# gps_tracker.net
KiCad netlist of a schematic drawn in EAGLE
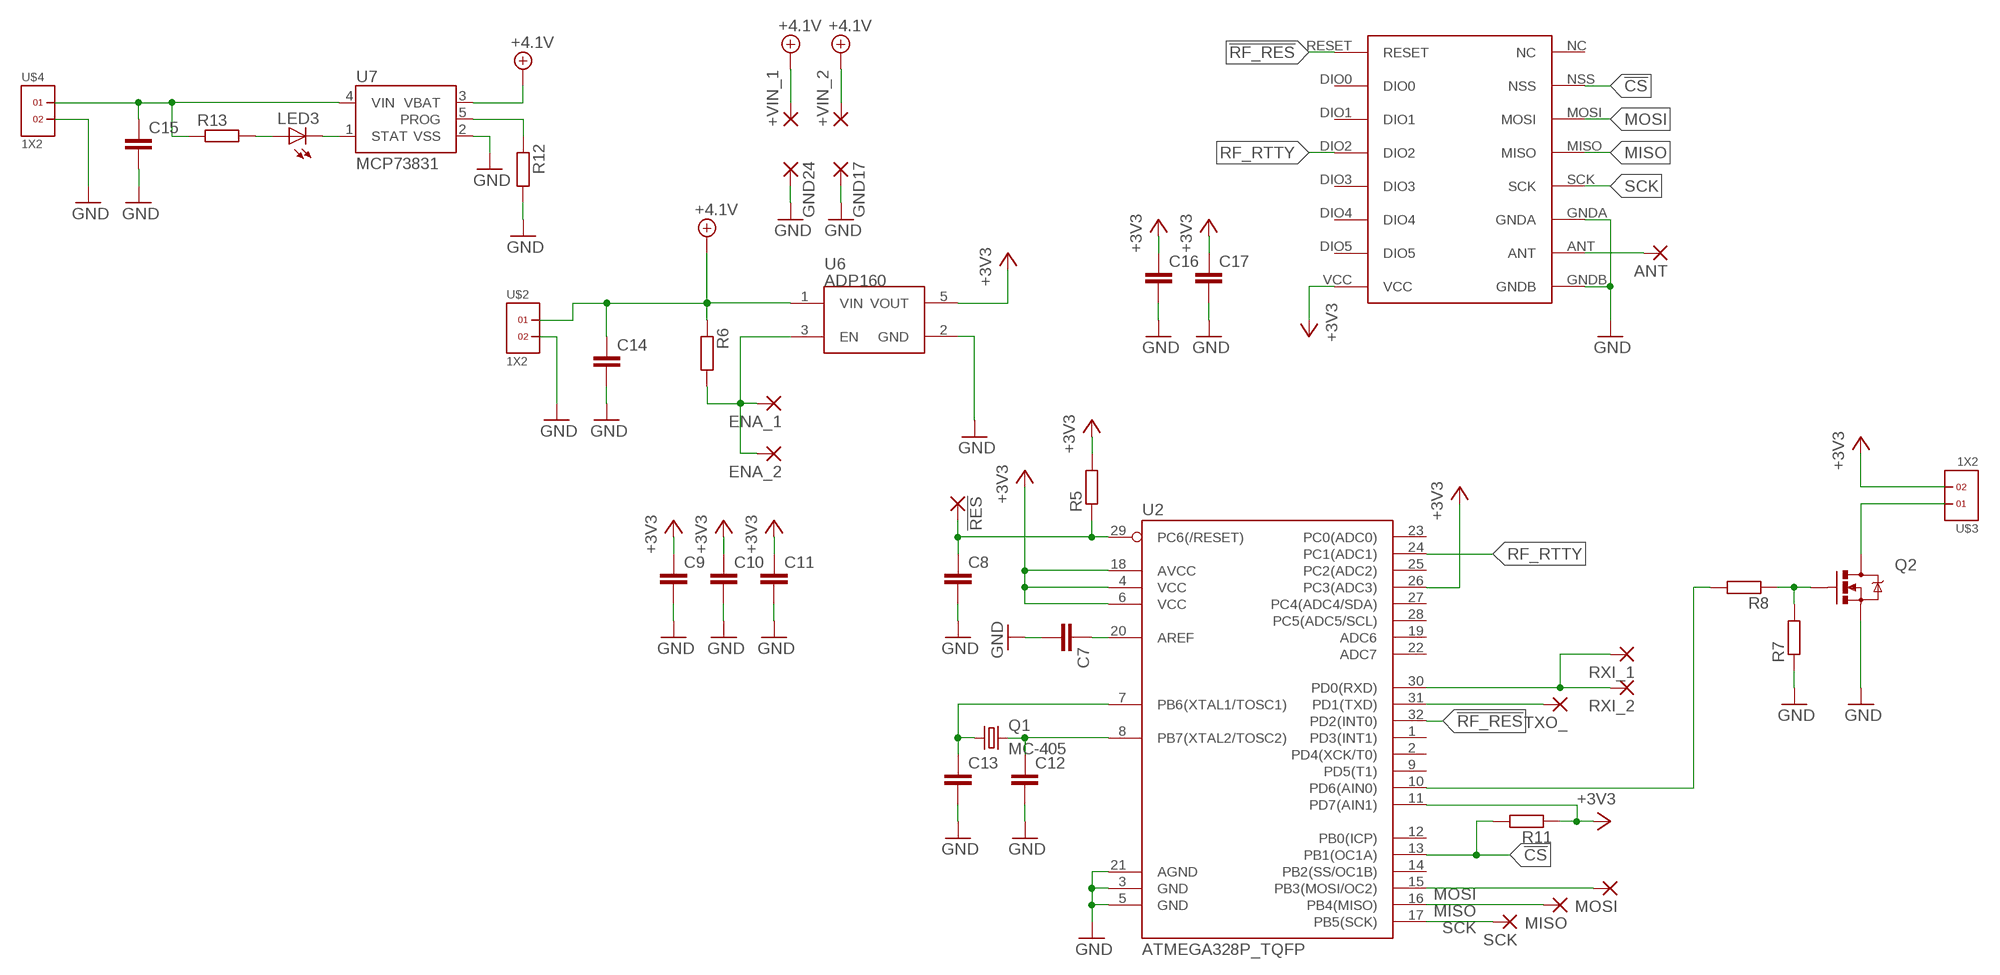
[diagram p0: schematic, sheet 1, part 1 of 2]
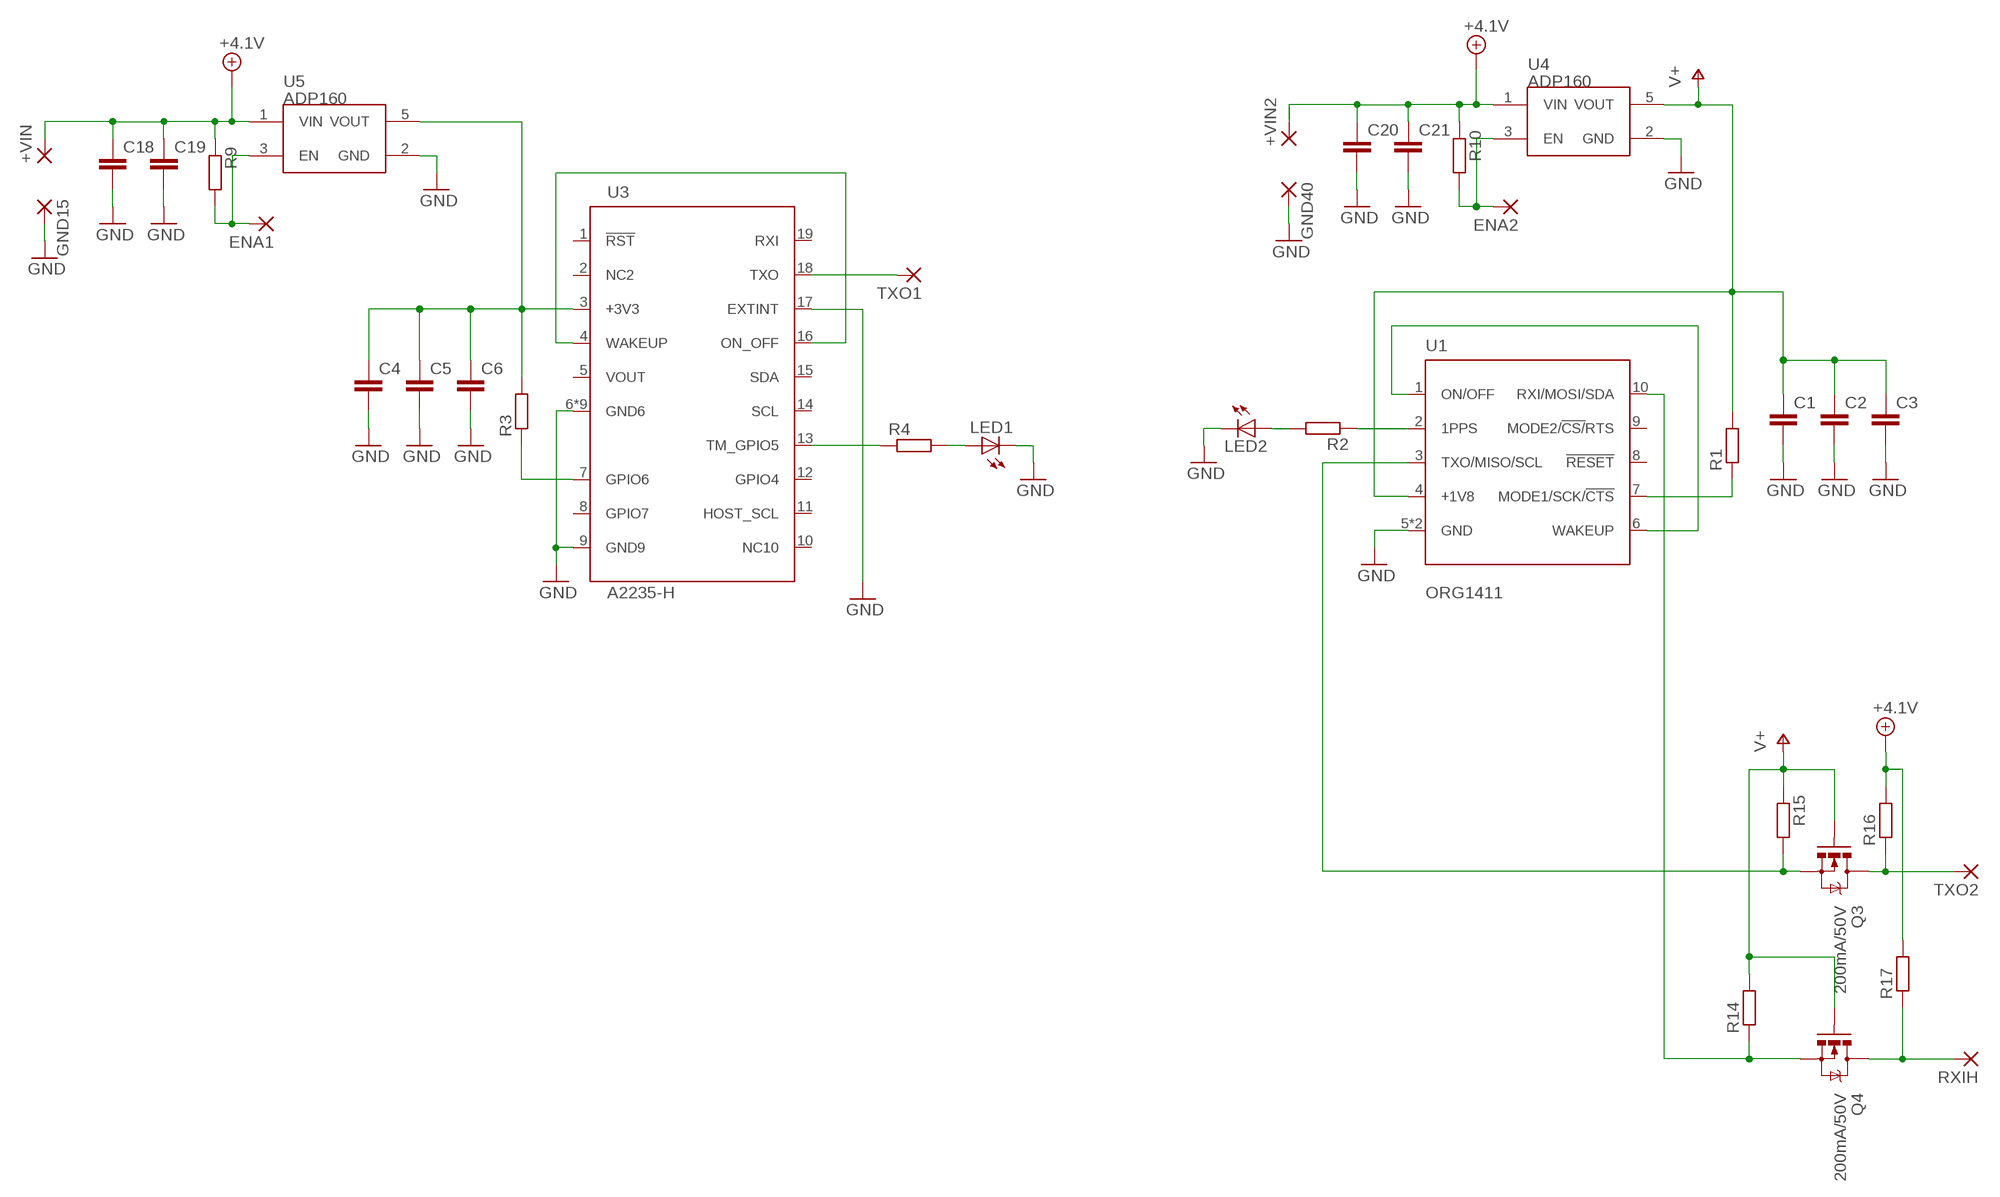
[diagram p1: schematic, sheet 1, part 2 of 2]
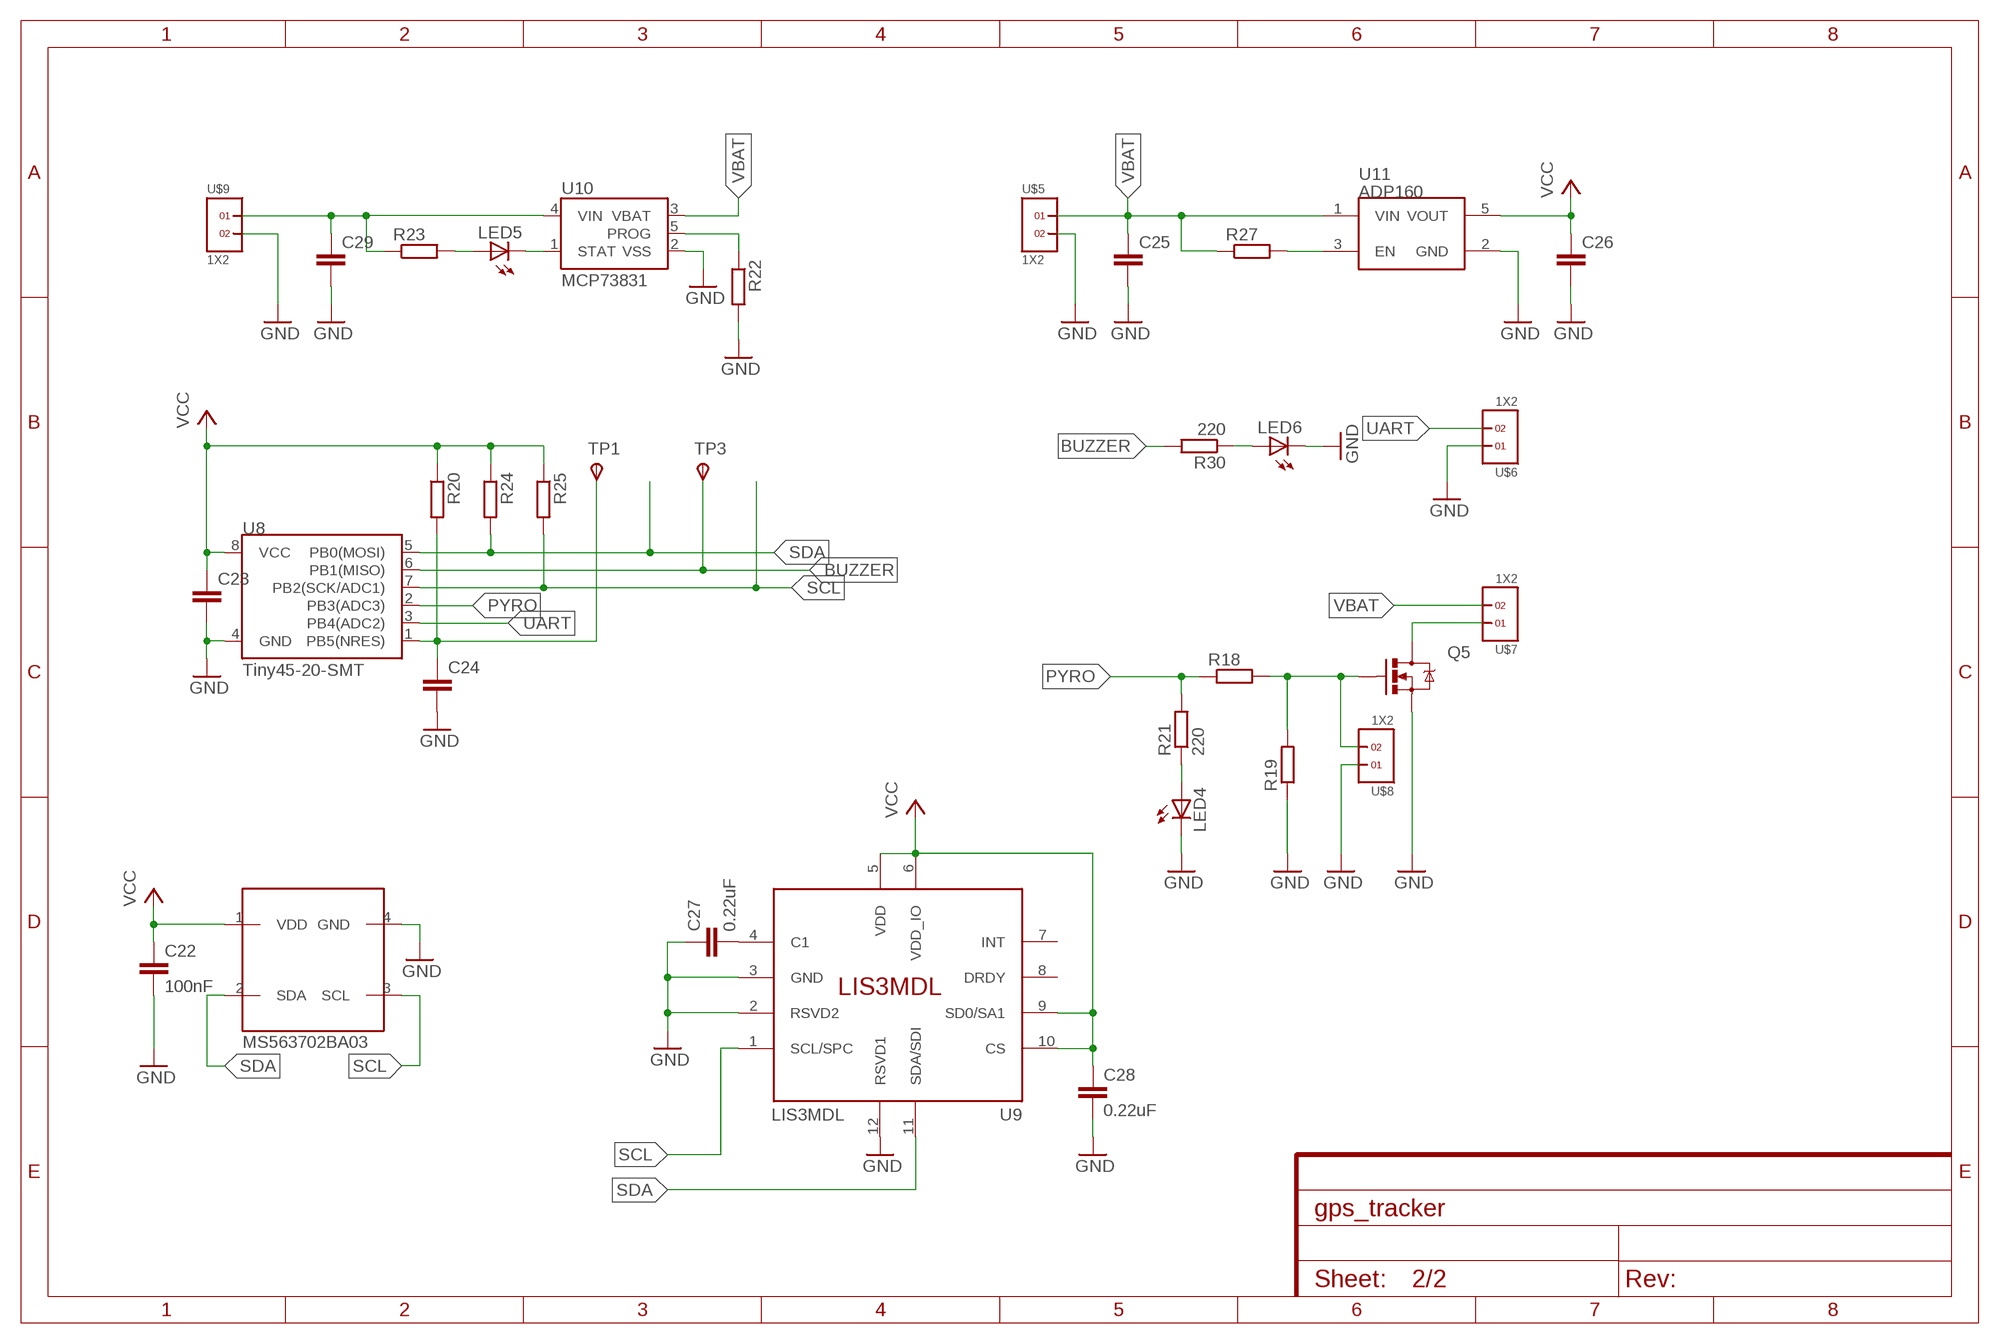
[diagram p2: schematic, sheet 2]

(export (version "E")
  (design (tool "Eeschema 10.0.6"))
  (components
    (comp (ref "C22")
      (value "100nF")
      (footprint "eagle-import:C0603")
      (libsource (lib "eagle-import") (part "C-EUC0603"))
    )
    (comp (ref "C23")
      (value "C-EUC1206")
      (footprint "eagle-import:C1206")
      (libsource (lib "eagle-import") (part "C-EUC1206"))
    )
    (comp (ref "C24")
      (value "C-EUC0603")
      (footprint "eagle-import:C0603")
      (libsource (lib "eagle-import") (part "C-EUC0603"))
    )
    (comp (ref "C25")
      (value "C-EUC0603")
      (footprint "eagle-import:C0603")
      (libsource (lib "eagle-import") (part "C-EUC0603"))
    )
    (comp (ref "C26")
      (value "C-EUC0603")
      (footprint "eagle-import:C0603")
      (libsource (lib "eagle-import") (part "C-EUC0603"))
    )
    (comp (ref "C27")
      (value "0.22uF")
      (footprint "eagle-import:C0603K")
      (libsource (lib "eagle-import") (part "C-EUC0603K"))
    )
    (comp (ref "C28")
      (value "0.22uF")
      (footprint "eagle-import:C0603")
      (libsource (lib "eagle-import") (part "C-EUC0603"))
    )
    (comp (ref "C29")
      (value "C-EUC0603")
      (footprint "eagle-import:C0603")
      (libsource (lib "eagle-import") (part "C-EUC0603"))
    )
    (comp (ref "IC1")
      (value "MS563702BA03")
      (footprint "eagle-import:MS5637")
      (libsource (lib "eagle-import") (part "MS563702BA03"))
    )
    (comp (ref "LED4")
      (value "LEDCHIPLED_0805")
      (footprint "eagle-import:CHIPLED_0805")
      (libsource (lib "eagle-import") (part "LEDCHIPLED_0805"))
    )
    (comp (ref "LED5")
      (value "LEDCHIPLED_0603")
      (footprint "eagle-import:CHIPLED_0603")
      (libsource (lib "eagle-import") (part "LEDCHIPLED_0603"))
    )
    (comp (ref "LED6")
      (value "LEDCHIPLED_0805")
      (footprint "eagle-import:CHIPLED_0805")
      (libsource (lib "eagle-import") (part "LEDCHIPLED_0805"))
    )
    (comp (ref "Q5")
      (value "MOSFET-NCHANNELBSS123LT1G")
      (footprint "eagle-import:SOT23-3")
      (libsource (lib "eagle-import") (part "MOSFET-NCHANNELBSS123LT1G"))
    )
    (comp (ref "R18")
      (value "R-EU_R0603")
      (footprint "eagle-import:R0603")
      (libsource (lib "eagle-import") (part "R-EU_R0603"))
    )
    (comp (ref "R19")
      (value "R-EU_R0603")
      (footprint "eagle-import:R0603")
      (libsource (lib "eagle-import") (part "R-EU_R0603"))
    )
    (comp (ref "R20")
      (value "R-EU_R0603")
      (footprint "eagle-import:R0603")
      (libsource (lib "eagle-import") (part "R-EU_R0603"))
    )
    (comp (ref "R21")
      (value "220")
      (footprint "eagle-import:R0603")
      (libsource (lib "eagle-import") (part "resistor_R-EU_R0603"))
    )
    (comp (ref "R22")
      (value "R-EU_R0603")
      (footprint "eagle-import:R0603")
      (libsource (lib "eagle-import") (part "R-EU_R0603"))
    )
    (comp (ref "R23")
      (value "R-EU_R0603")
      (footprint "eagle-import:R0603")
      (libsource (lib "eagle-import") (part "R-EU_R0603"))
    )
    (comp (ref "R24")
      (value "R-EU_R0603")
      (footprint "eagle-import:R0603")
      (libsource (lib "eagle-import") (part "R-EU_R0603"))
    )
    (comp (ref "R25")
      (value "R-EU_R0603")
      (footprint "eagle-import:R0603")
      (libsource (lib "eagle-import") (part "R-EU_R0603"))
    )
    (comp (ref "R27")
      (value "R-EU_R0603")
      (footprint "eagle-import:R0603")
      (libsource (lib "eagle-import") (part "R-EU_R0603"))
    )
    (comp (ref "R30")
      (value "220")
      (footprint "eagle-import:R0603")
      (libsource (lib "eagle-import") (part "resistor_R-EU_R0603"))
    )
    (comp (ref "TP1")
      (value "TPSB1,27")
      (footprint "eagle-import:B1,27")
      (libsource (lib "eagle-import") (part "TPSB1,27"))
    )
    (comp (ref "TP3")
      (value "TPSB1,27")
      (footprint "eagle-import:B1,27")
      (libsource (lib "eagle-import") (part "TPSB1,27"))
    )
    (comp (ref "U$5")
      (value "1X2")
      (footprint "eagle-import:1X2")
      (libsource (lib "eagle-import") (part "1X2"))
    )
    (comp (ref "U$6")
      (value "1X2")
      (footprint "eagle-import:1X2")
      (libsource (lib "eagle-import") (part "1X2"))
    )
    (comp (ref "U$7")
      (value "1X2")
      (footprint "eagle-import:1X2")
      (libsource (lib "eagle-import") (part "1X2"))
    )
    (comp (ref "U$8")
      (value "1X2")
      (footprint "eagle-import:1X2")
      (libsource (lib "eagle-import") (part "1X2"))
    )
    (comp (ref "U$9")
      (value "1X2")
      (footprint "eagle-import:1X2")
      (libsource (lib "eagle-import") (part "1X2"))
    )
    (comp (ref "U8")
      (value "Tiny45-20-SMT")
      (footprint "eagle-import:SO08-EIAJ")
      (libsource (lib "eagle-import") (part "ATTINY45TINY45-20-SMT"))
    )
    (comp (ref "U9")
      (value "LIS3MDL")
      (footprint "eagle-import:VFLGA-12")
      (libsource (lib "eagle-import") (part "LIS3MDL"))
    )
    (comp (ref "U10")
      (value "MCP73831")
      (footprint "eagle-import:SOT23-5")
      (libsource (lib "eagle-import") (part "MCP73831"))
    )
    (comp (ref "U11")
      (value "ADP160")
      (footprint "eagle-import:SOT23-5")
      (libsource (lib "eagle-import") (part "ADP160"))
    )
    (comp (ref "!RES")
      (value "SMD2")
      (footprint "eagle-import:SMD1,27-2,54")
      (libsource (lib "eagle-import") (part "SMD2"))
    )
    (comp (ref "+VIN")
      (value "SMD2")
      (footprint "eagle-import:SMD1,27-2,54")
      (libsource (lib "eagle-import") (part "SMD2"))
    )
    (comp (ref "+VIN2")
      (value "SMD2")
      (footprint "eagle-import:SMD1,27-2,54")
      (libsource (lib "eagle-import") (part "SMD2"))
    )
    (comp (ref "+VIN_1")
      (value "SMD2")
      (footprint "eagle-import:SMD1,27-2,54")
      (libsource (lib "eagle-import") (part "SMD2"))
    )
    (comp (ref "+VIN_2")
      (value "SMD2")
      (footprint "eagle-import:SMD1,27-2,54")
      (libsource (lib "eagle-import") (part "SMD2"))
    )
    (comp (ref "ANT")
      (value "SMD2")
      (footprint "eagle-import:SMD1,27-2,54")
      (libsource (lib "eagle-import") (part "SMD2"))
    )
    (comp (ref "C1")
      (value "C-EUC0603")
      (footprint "eagle-import:C0603")
      (libsource (lib "eagle-import") (part "C-EUC0603"))
    )
    (comp (ref "C2")
      (value "C-EUC0603")
      (footprint "eagle-import:C0603")
      (libsource (lib "eagle-import") (part "C-EUC0603"))
    )
    (comp (ref "C3")
      (value "C-EUC0603")
      (footprint "eagle-import:C0603")
      (libsource (lib "eagle-import") (part "C-EUC0603"))
    )
    (comp (ref "C4")
      (value "C-EUC0603")
      (footprint "eagle-import:C0603")
      (libsource (lib "eagle-import") (part "C-EUC0603"))
    )
    (comp (ref "C5")
      (value "C-EUC0603")
      (footprint "eagle-import:C0603")
      (libsource (lib "eagle-import") (part "C-EUC0603"))
    )
    (comp (ref "C6")
      (value "C-EUC0603")
      (footprint "eagle-import:C0603")
      (libsource (lib "eagle-import") (part "C-EUC0603"))
    )
    (comp (ref "C7")
      (value "C-EUC0603")
      (footprint "eagle-import:C0603")
      (libsource (lib "eagle-import") (part "C-EUC0603"))
    )
    (comp (ref "C8")
      (value "C-EUC0603")
      (footprint "eagle-import:C0603")
      (libsource (lib "eagle-import") (part "C-EUC0603"))
    )
    (comp (ref "C9")
      (value "C-EUC0603")
      (footprint "eagle-import:C0603")
      (libsource (lib "eagle-import") (part "C-EUC0603"))
    )
    (comp (ref "C10")
      (value "C-EUC0603")
      (footprint "eagle-import:C0603")
      (libsource (lib "eagle-import") (part "C-EUC0603"))
    )
    (comp (ref "C11")
      (value "C-EUC0603")
      (footprint "eagle-import:C0603")
      (libsource (lib "eagle-import") (part "C-EUC0603"))
    )
    (comp (ref "C12")
      (value "C-EUC0603")
      (footprint "eagle-import:C0603")
      (libsource (lib "eagle-import") (part "C-EUC0603"))
    )
    (comp (ref "C13")
      (value "C-EUC0603")
      (footprint "eagle-import:C0603")
      (libsource (lib "eagle-import") (part "C-EUC0603"))
    )
    (comp (ref "C14")
      (value "C-EUC0603")
      (footprint "eagle-import:C0603")
      (libsource (lib "eagle-import") (part "C-EUC0603"))
    )
    (comp (ref "C15")
      (value "C-EUC0603")
      (footprint "eagle-import:C0603")
      (libsource (lib "eagle-import") (part "C-EUC0603"))
    )
    (comp (ref "C16")
      (value "C-EUC0603")
      (footprint "eagle-import:C0603")
      (libsource (lib "eagle-import") (part "C-EUC0603"))
    )
    (comp (ref "C17")
      (value "C-EUC0603")
      (footprint "eagle-import:C0603")
      (libsource (lib "eagle-import") (part "C-EUC0603"))
    )
    (comp (ref "C18")
      (value "C-EUC0603")
      (footprint "eagle-import:C0603")
      (libsource (lib "eagle-import") (part "C-EUC0603"))
    )
    (comp (ref "C19")
      (value "C-EUC0603")
      (footprint "eagle-import:C0603")
      (libsource (lib "eagle-import") (part "C-EUC0603"))
    )
    (comp (ref "C20")
      (value "C-EUC0603")
      (footprint "eagle-import:C0603")
      (libsource (lib "eagle-import") (part "C-EUC0603"))
    )
    (comp (ref "C21")
      (value "C-EUC0603")
      (footprint "eagle-import:C0603")
      (libsource (lib "eagle-import") (part "C-EUC0603"))
    )
    (comp (ref "ENA1")
      (value "SMD2")
      (footprint "eagle-import:SMD1,27-2,54")
      (libsource (lib "eagle-import") (part "SMD2"))
    )
    (comp (ref "ENA2")
      (value "SMD2")
      (footprint "eagle-import:SMD1,27-2,54")
      (libsource (lib "eagle-import") (part "SMD2"))
    )
    (comp (ref "ENA_1")
      (value "SMD2")
      (footprint "eagle-import:SMD1,27-2,54")
      (libsource (lib "eagle-import") (part "SMD2"))
    )
    (comp (ref "ENA_2")
      (value "SMD2")
      (footprint "eagle-import:SMD1,27-2,54")
      (libsource (lib "eagle-import") (part "SMD2"))
    )
    (comp (ref "GND15")
      (value "SMD2")
      (footprint "eagle-import:SMD1,27-2,54")
      (libsource (lib "eagle-import") (part "SMD2"))
    )
    (comp (ref "GND17")
      (value "SMD2")
      (footprint "eagle-import:SMD1,27-2,54")
      (libsource (lib "eagle-import") (part "SMD2"))
    )
    (comp (ref "GND24")
      (value "SMD2")
      (footprint "eagle-import:SMD1,27-2,54")
      (libsource (lib "eagle-import") (part "SMD2"))
    )
    (comp (ref "GND40")
      (value "SMD2")
      (footprint "eagle-import:SMD1,27-2,54")
      (libsource (lib "eagle-import") (part "SMD2"))
    )
    (comp (ref "LED1")
      (value "LEDCHIPLED_0603")
      (footprint "eagle-import:CHIPLED_0603")
      (libsource (lib "eagle-import") (part "LEDCHIPLED_0603"))
    )
    (comp (ref "LED2")
      (value "LEDCHIPLED_0603")
      (footprint "eagle-import:CHIPLED_0603")
      (libsource (lib "eagle-import") (part "LEDCHIPLED_0603"))
    )
    (comp (ref "LED3")
      (value "LEDCHIPLED_0603")
      (footprint "eagle-import:CHIPLED_0603")
      (libsource (lib "eagle-import") (part "LEDCHIPLED_0603"))
    )
    (comp (ref "MISO")
      (value "SMD2")
      (footprint "eagle-import:SMD1,27-2,54")
      (libsource (lib "eagle-import") (part "SMD2"))
    )
    (comp (ref "MOSI")
      (value "SMD2")
      (footprint "eagle-import:SMD1,27-2,54")
      (libsource (lib "eagle-import") (part "SMD2"))
    )
    (comp (ref "Q1")
      (value "MC-405")
      (footprint "eagle-import:MC-405")
      (libsource (lib "eagle-import") (part "MC-405"))
    )
    (comp (ref "Q2")
      (value "MOSFET-NCHANNELAO3404A")
      (footprint "eagle-import:SOT23-3")
      (libsource (lib "eagle-import") (part "MOSFET-NCHANNELAO3404A"))
    )
    (comp (ref "Q3")
      (value "200mA/50V")
      (footprint "eagle-import:SOT23-3")
      (libsource (lib "eagle-import") (part "MOSFET-NCHANNELBSS138"))
    )
    (comp (ref "Q4")
      (value "200mA/50V")
      (footprint "eagle-import:SOT23-3")
      (libsource (lib "eagle-import") (part "MOSFET-NCHANNELBSS138"))
    )
    (comp (ref "R1")
      (value "R-EU_R0603")
      (footprint "eagle-import:R0603")
      (libsource (lib "eagle-import") (part "R-EU_R0603"))
    )
    (comp (ref "R2")
      (value "R-EU_R0603")
      (footprint "eagle-import:R0603")
      (libsource (lib "eagle-import") (part "R-EU_R0603"))
    )
    (comp (ref "R3")
      (value "R-EU_R0603")
      (footprint "eagle-import:R0603")
      (libsource (lib "eagle-import") (part "R-EU_R0603"))
    )
    (comp (ref "R4")
      (value "R-EU_R0603")
      (footprint "eagle-import:R0603")
      (libsource (lib "eagle-import") (part "R-EU_R0603"))
    )
    (comp (ref "R5")
      (value "R-EU_R0603")
      (footprint "eagle-import:R0603")
      (libsource (lib "eagle-import") (part "R-EU_R0603"))
    )
    (comp (ref "R6")
      (value "R-EU_R0603")
      (footprint "eagle-import:R0603")
      (libsource (lib "eagle-import") (part "R-EU_R0603"))
    )
    (comp (ref "R7")
      (value "R-EU_R0603")
      (footprint "eagle-import:R0603")
      (libsource (lib "eagle-import") (part "R-EU_R0603"))
    )
    (comp (ref "R8")
      (value "R-EU_R0603")
      (footprint "eagle-import:R0603")
      (libsource (lib "eagle-import") (part "R-EU_R0603"))
    )
    (comp (ref "R9")
      (value "R-EU_R0603")
      (footprint "eagle-import:R0603")
      (libsource (lib "eagle-import") (part "R-EU_R0603"))
    )
    (comp (ref "R10")
      (value "R-EU_R0603")
      (footprint "eagle-import:R0603")
      (libsource (lib "eagle-import") (part "R-EU_R0603"))
    )
    (comp (ref "R11")
      (value "R-EU_R0603")
      (footprint "eagle-import:R0603")
      (libsource (lib "eagle-import") (part "R-EU_R0603"))
    )
    (comp (ref "R12")
      (value "R-EU_R0603")
      (footprint "eagle-import:R0603")
      (libsource (lib "eagle-import") (part "R-EU_R0603"))
    )
    (comp (ref "R13")
      (value "R-EU_R0603")
      (footprint "eagle-import:R0603")
      (libsource (lib "eagle-import") (part "R-EU_R0603"))
    )
    (comp (ref "R14")
      (value "R-EU_R0603")
      (footprint "eagle-import:R0603")
      (libsource (lib "eagle-import") (part "R-EU_R0603"))
    )
    (comp (ref "R15")
      (value "R-EU_R0603")
      (footprint "eagle-import:R0603")
      (libsource (lib "eagle-import") (part "R-EU_R0603"))
    )
    (comp (ref "R16")
      (value "R-EU_R1206")
      (footprint "eagle-import:R1206")
      (libsource (lib "eagle-import") (part "R-EU_R1206"))
    )
    (comp (ref "R17")
      (value "R-EU_R1206")
      (footprint "eagle-import:R1206")
      (libsource (lib "eagle-import") (part "R-EU_R1206"))
    )
    (comp (ref "RXIH")
      (value "SMD2")
      (footprint "eagle-import:SMD1,27-2,54")
      (libsource (lib "eagle-import") (part "SMD2"))
    )
    (comp (ref "RXI_1")
      (value "SMD2")
      (footprint "eagle-import:SMD1,27-2,54")
      (libsource (lib "eagle-import") (part "SMD2"))
    )
    (comp (ref "RXI_2")
      (value "SMD2")
      (footprint "eagle-import:SMD1,27-2,54")
      (libsource (lib "eagle-import") (part "SMD2"))
    )
    (comp (ref "SCK")
      (value "SMD2")
      (footprint "eagle-import:SMD1,27-2,54")
      (libsource (lib "eagle-import") (part "SMD2"))
    )
    (comp (ref "TXO1")
      (value "SMD2")
      (footprint "eagle-import:SMD1,27-2,54")
      (libsource (lib "eagle-import") (part "SMD2"))
    )
    (comp (ref "TXO2")
      (value "SMD2")
      (footprint "eagle-import:SMD1,27-2,54")
      (libsource (lib "eagle-import") (part "SMD2"))
    )
    (comp (ref "TXO_")
      (value "SMD2")
      (footprint "eagle-import:SMD1,27-2,54")
      (libsource (lib "eagle-import") (part "SMD2"))
    )
    (comp (ref "U$1")
      (value "RFM69HW")
      (footprint "eagle-import:RFM")
      (libsource (lib "eagle-import") (part "RFM69HW"))
    )
    (comp (ref "U$2")
      (value "1X2")
      (footprint "eagle-import:1X2")
      (libsource (lib "eagle-import") (part "1X2"))
    )
    (comp (ref "U$3")
      (value "1X2")
      (footprint "eagle-import:1X2")
      (libsource (lib "eagle-import") (part "1X2"))
    )
    (comp (ref "U$4")
      (value "1X2")
      (footprint "eagle-import:1X2")
      (libsource (lib "eagle-import") (part "1X2"))
    )
    (comp (ref "U1")
      (value "ORG1411")
      (footprint "eagle-import:ORG1411")
      (libsource (lib "eagle-import") (part "ORG1411"))
    )
    (comp (ref "U2")
      (value "ATMEGA328P_TQFP")
      (footprint "eagle-import:TQFP32-08")
      (libsource (lib "eagle-import") (part "ATMEGA328P_TQFP"))
    )
    (comp (ref "U3")
      (value "A2235-H")
      (footprint "eagle-import:A2235-H")
      (libsource (lib "eagle-import") (part "A2235-H"))
    )
    (comp (ref "U4")
      (value "ADP160")
      (footprint "eagle-import:SOT23-5")
      (libsource (lib "eagle-import") (part "ADP160"))
    )
    (comp (ref "U5")
      (value "ADP160")
      (footprint "eagle-import:SOT23-5")
      (libsource (lib "eagle-import") (part "ADP160"))
    )
    (comp (ref "U6")
      (value "ADP160")
      (footprint "eagle-import:SOT23-5")
      (libsource (lib "eagle-import") (part "ADP160"))
    )
    (comp (ref "U7")
      (value "MCP73831")
      (footprint "eagle-import:SOT23-5")
      (libsource (lib "eagle-import") (part "MCP73831"))
    )
  )
  (nets
    (net (code "1") (name "+3V3") (class "Default")
      (node (ref "C10") (pin "1") (pinfunction "1_1") (pintype "passive"))
      (node (ref "C11") (pin "1") (pinfunction "1_1") (pintype "passive"))
      (node (ref "C16") (pin "1") (pinfunction "1_1") (pintype "passive"))
      (node (ref "C17") (pin "1") (pinfunction "1_1") (pintype "passive"))
      (node (ref "C9") (pin "1") (pinfunction "1_1") (pintype "passive"))
      (node (ref "R11") (pin "1") (pinfunction "1_1") (pintype "passive"))
      (node (ref "R5") (pin "2") (pinfunction "2_2") (pintype "passive"))
      (node (ref "U$1") (pin "VCC") (pinfunction "VCC_VCC") (pintype "bidirectional"))
      (node (ref "U$3") (pin "2") (pinfunction "2_2") (pintype "bidirectional"))
      (node (ref "U2") (pin "11") (pinfunction "PD7(AIN1)_11") (pintype "bidirectional"))
      (node (ref "U2") (pin "18") (pinfunction "AVCC_18") (pintype "bidirectional"))
      (node (ref "U2") (pin "26") (pinfunction "PC3(ADC3)_26") (pintype "bidirectional"))
      (node (ref "U2") (pin "4") (pinfunction "VCC_4") (pintype "bidirectional"))
      (node (ref "U2") (pin "6") (pinfunction "VCC_6") (pintype "bidirectional"))
      (node (ref "U6") (pin "5") (pinfunction "VOUT_5") (pintype "bidirectional"))
    )
    (net (code "2") (name "+4.1V") (class "Default")
      (node (ref "+VIN") (pin "1") (pinfunction "P_1") (pintype "passive"))
      (node (ref "+VIN2") (pin "1") (pinfunction "P_1") (pintype "passive"))
      (node (ref "+VIN_1") (pin "1") (pinfunction "P_1") (pintype "passive"))
      (node (ref "+VIN_2") (pin "1") (pinfunction "P_1") (pintype "passive"))
      (node (ref "C14") (pin "1") (pinfunction "1_1") (pintype "passive"))
      (node (ref "C18") (pin "1") (pinfunction "1_1") (pintype "passive"))
      (node (ref "C19") (pin "1") (pinfunction "1_1") (pintype "passive"))
      (node (ref "C20") (pin "1") (pinfunction "1_1") (pintype "passive"))
      (node (ref "C21") (pin "1") (pinfunction "1_1") (pintype "passive"))
      (node (ref "R10") (pin "1") (pinfunction "1_1") (pintype "passive"))
      (node (ref "R16") (pin "2") (pinfunction "2_2") (pintype "passive"))
      (node (ref "R17") (pin "2") (pinfunction "2_2") (pintype "passive"))
      (node (ref "R6") (pin "1") (pinfunction "1_1") (pintype "passive"))
      (node (ref "R9") (pin "1") (pinfunction "1_1") (pintype "passive"))
      (node (ref "U$2") (pin "1") (pinfunction "1_1") (pintype "bidirectional"))
      (node (ref "U4") (pin "1") (pinfunction "VIN_1") (pintype "bidirectional"))
      (node (ref "U5") (pin "1") (pinfunction "VIN_1") (pintype "bidirectional"))
      (node (ref "U6") (pin "1") (pinfunction "VIN_1") (pintype "bidirectional"))
      (node (ref "U7") (pin "3") (pinfunction "VBAT_3") (pintype "power_in"))
    )
    (net (code "3") (name "BUZZER") (class "Default")
      (node (ref "R30") (pin "2") (pinfunction "2_2") (pintype "passive"))
      (node (ref "TP3") (pin "TP") (pinfunction "PP_TP") (pintype "input"))
      (node (ref "U8") (pin "6") (pinfunction "PB1(MISO)_6") (pintype "bidirectional"))
    )
    (net (code "4") (name "GND") (class "Default")
      (node (ref "C1") (pin "2") (pinfunction "2_2") (pintype "passive"))
      (node (ref "C10") (pin "2") (pinfunction "2_2") (pintype "passive"))
      (node (ref "C11") (pin "2") (pinfunction "2_2") (pintype "passive"))
      (node (ref "C12") (pin "2") (pinfunction "2_2") (pintype "passive"))
      (node (ref "C13") (pin "2") (pinfunction "2_2") (pintype "passive"))
      (node (ref "C14") (pin "2") (pinfunction "2_2") (pintype "passive"))
      (node (ref "C15") (pin "2") (pinfunction "2_2") (pintype "passive"))
      (node (ref "C16") (pin "2") (pinfunction "2_2") (pintype "passive"))
      (node (ref "C17") (pin "2") (pinfunction "2_2") (pintype "passive"))
      (node (ref "C18") (pin "2") (pinfunction "2_2") (pintype "passive"))
      (node (ref "C19") (pin "2") (pinfunction "2_2") (pintype "passive"))
      (node (ref "C2") (pin "2") (pinfunction "2_2") (pintype "passive"))
      (node (ref "C20") (pin "2") (pinfunction "2_2") (pintype "passive"))
      (node (ref "C21") (pin "2") (pinfunction "2_2") (pintype "passive"))
      (node (ref "C22") (pin "2") (pinfunction "2_2") (pintype "passive"))
      (node (ref "C23") (pin "2") (pinfunction "2_2") (pintype "passive"))
      (node (ref "C24") (pin "2") (pinfunction "2_2") (pintype "passive"))
      (node (ref "C25") (pin "2") (pinfunction "2_2") (pintype "passive"))
      (node (ref "C26") (pin "2") (pinfunction "2_2") (pintype "passive"))
      (node (ref "C27") (pin "1") (pinfunction "1_1") (pintype "passive"))
      (node (ref "C28") (pin "2") (pinfunction "2_2") (pintype "passive"))
      (node (ref "C29") (pin "2") (pinfunction "2_2") (pintype "passive"))
      (node (ref "C3") (pin "2") (pinfunction "2_2") (pintype "passive"))
      (node (ref "C4") (pin "2") (pinfunction "2_2") (pintype "passive"))
      (node (ref "C5") (pin "2") (pinfunction "2_2") (pintype "passive"))
      (node (ref "C6") (pin "2") (pinfunction "2_2") (pintype "passive"))
      (node (ref "C7") (pin "2") (pinfunction "2_2") (pintype "passive"))
      (node (ref "C8") (pin "2") (pinfunction "2_2") (pintype "passive"))
      (node (ref "C9") (pin "2") (pinfunction "2_2") (pintype "passive"))
      (node (ref "GND15") (pin "1") (pinfunction "P_1") (pintype "passive"))
      (node (ref "GND17") (pin "1") (pinfunction "P_1") (pintype "passive"))
      (node (ref "GND24") (pin "1") (pinfunction "P_1") (pintype "passive"))
      (node (ref "GND40") (pin "1") (pinfunction "P_1") (pintype "passive"))
      (node (ref "IC1") (pin "4") (pinfunction "GND_4") (pintype "bidirectional"))
      (node (ref "LED1") (pin "C") (pinfunction "C_C") (pintype "passive"))
      (node (ref "LED2") (pin "C") (pinfunction "C_C") (pintype "passive"))
      (node (ref "LED4") (pin "C") (pinfunction "C_C") (pintype "passive"))
      (node (ref "LED6") (pin "C") (pinfunction "C_C") (pintype "passive"))
      (node (ref "Q2") (pin "2") (pinfunction "S_2") (pintype "passive"))
      (node (ref "Q5") (pin "2") (pinfunction "S_2") (pintype "passive"))
      (node (ref "R12") (pin "2") (pinfunction "2_2") (pintype "passive"))
      (node (ref "R19") (pin "1") (pinfunction "1_1") (pintype "passive"))
      (node (ref "R22") (pin "2") (pinfunction "2_2") (pintype "passive"))
      (node (ref "R7") (pin "1") (pinfunction "1_1") (pintype "passive"))
      (node (ref "U$1") (pin "GNDA") (pinfunction "GNDA_GNDA") (pintype "bidirectional"))
      (node (ref "U$1") (pin "GNDB") (pinfunction "GNDB_GNDB") (pintype "bidirectional"))
      (node (ref "U$2") (pin "2") (pinfunction "2_2") (pintype "bidirectional"))
      (node (ref "U$4") (pin "2") (pinfunction "2_2") (pintype "bidirectional"))
      (node (ref "U$5") (pin "2") (pinfunction "2_2") (pintype "bidirectional"))
      (node (ref "U$6") (pin "1") (pinfunction "1_1") (pintype "bidirectional"))
      (node (ref "U$8") (pin "1") (pinfunction "1_1") (pintype "bidirectional"))
      (node (ref "U$9") (pin "2") (pinfunction "2_2") (pintype "bidirectional"))
      (node (ref "U1") (pin "11") (pinfunction "GND_11") (pintype "power_in"))
      (node (ref "U1") (pin "5") (pinfunction "GND_5") (pintype "power_in"))
      (node (ref "U10") (pin "2") (pinfunction "VSS_2") (pintype "power_in"))
      (node (ref "U11") (pin "2") (pinfunction "GND_2") (pintype "bidirectional"))
      (node (ref "U2") (pin "21") (pinfunction "AGND_21") (pintype "bidirectional"))
      (node (ref "U2") (pin "3") (pinfunction "GND_3") (pintype "bidirectional"))
      (node (ref "U2") (pin "5") (pinfunction "GND_5") (pintype "bidirectional"))
      (node (ref "U3") (pin "101") (pinfunction "GND6_101") (pintype "power_in"))
      (node (ref "U3") (pin "102") (pinfunction "GND6_102") (pintype "power_in"))
      (node (ref "U3") (pin "103") (pinfunction "GND6_103") (pintype "power_in"))
      (node (ref "U3") (pin "104") (pinfunction "GND6_104") (pintype "power_in"))
      (node (ref "U3") (pin "105") (pinfunction "GND6_105") (pintype "power_in"))
      (node (ref "U3") (pin "106") (pinfunction "GND6_106") (pintype "power_in"))
      (node (ref "U3") (pin "107") (pinfunction "GND6_107") (pintype "power_in"))
      (node (ref "U3") (pin "108") (pinfunction "GND6_108") (pintype "power_in"))
      (node (ref "U3") (pin "17") (pinfunction "EXTINT_17") (pintype "input"))
      (node (ref "U3") (pin "6") (pinfunction "GND6_6") (pintype "power_in"))
      (node (ref "U3") (pin "9") (pinfunction "GND9_9") (pintype "power_in"))
      (node (ref "U4") (pin "2") (pinfunction "GND_2") (pintype "bidirectional"))
      (node (ref "U5") (pin "2") (pinfunction "GND_2") (pintype "bidirectional"))
      (node (ref "U6") (pin "2") (pinfunction "GND_2") (pintype "bidirectional"))
      (node (ref "U7") (pin "2") (pinfunction "VSS_2") (pintype "power_in"))
      (node (ref "U8") (pin "4") (pinfunction "GND_4") (pintype "bidirectional"))
      (node (ref "U9") (pin "12") (pinfunction "RSVD1_12") (pintype "bidirectional"))
      (node (ref "U9") (pin "2") (pinfunction "RSVD2_2") (pintype "bidirectional"))
      (node (ref "U9") (pin "3") (pinfunction "GND_3") (pintype "power_in"))
    )
    (net (code "5") (name "MISO") (class "Default")
      (node (ref "MISO") (pin "1") (pinfunction "P_1") (pintype "passive"))
      (node (ref "U$1") (pin "MISO") (pinfunction "MISO_MISO") (pintype "bidirectional"))
      (node (ref "U2") (pin "16") (pinfunction "PB4(MISO)_16") (pintype "bidirectional"))
    )
    (net (code "6") (name "MOSI") (class "Default")
      (node (ref "MOSI") (pin "1") (pinfunction "P_1") (pintype "passive"))
      (node (ref "U$1") (pin "MOSI") (pinfunction "MOSI_MOSI") (pintype "bidirectional"))
      (node (ref "U2") (pin "15") (pinfunction "PB3(MOSI/OC2)_15") (pintype "bidirectional"))
    )
    (net (code "7") (name "Net-(!RES-P)") (class "Default")
      (node (ref "!RES") (pin "1") (pinfunction "P_1") (pintype "passive"))
      (node (ref "C8") (pin "1") (pinfunction "1_1") (pintype "passive"))
      (node (ref "R5") (pin "1") (pinfunction "1_1") (pintype "passive"))
      (node (ref "U2") (pin "29") (pinfunction "PC6(/RESET)_29") (pintype "bidirectional"))
    )
    (net (code "8") (name "Net-(ANT-P)") (class "Default")
      (node (ref "ANT") (pin "1") (pinfunction "P_1") (pintype "passive"))
      (node (ref "U$1") (pin "ANT") (pinfunction "ANT_ANT") (pintype "bidirectional"))
    )
    (net (code "9") (name "Net-(ENA1-P)") (class "Default")
      (node (ref "ENA1") (pin "1") (pinfunction "P_1") (pintype "passive"))
      (node (ref "R9") (pin "2") (pinfunction "2_2") (pintype "passive"))
      (node (ref "U5") (pin "3") (pinfunction "EN_3") (pintype "bidirectional"))
    )
    (net (code "10") (name "Net-(ENA2-P)") (class "Default")
      (node (ref "ENA2") (pin "1") (pinfunction "P_1") (pintype "passive"))
      (node (ref "R10") (pin "2") (pinfunction "2_2") (pintype "passive"))
      (node (ref "U4") (pin "3") (pinfunction "EN_3") (pintype "bidirectional"))
    )
    (net (code "11") (name "Net-(ENA_1-P)") (class "Default")
      (node (ref "ENA_1") (pin "1") (pinfunction "P_1") (pintype "passive"))
      (node (ref "ENA_2") (pin "1") (pinfunction "P_1") (pintype "passive"))
      (node (ref "R6") (pin "2") (pinfunction "2_2") (pintype "passive"))
      (node (ref "U6") (pin "3") (pinfunction "EN_3") (pintype "bidirectional"))
    )
    (net (code "12") (name "Net-(LED1-PadA)") (class "Default")
      (node (ref "LED1") (pin "A") (pinfunction "A_A") (pintype "passive"))
      (node (ref "R4") (pin "2") (pinfunction "2_2") (pintype "passive"))
    )
    (net (code "13") (name "Net-(LED2-PadA)") (class "Default")
      (node (ref "LED2") (pin "A") (pinfunction "A_A") (pintype "passive"))
      (node (ref "R2") (pin "2") (pinfunction "2_2") (pintype "passive"))
    )
    (net (code "14") (name "Net-(LED3-PadA)") (class "Default")
      (node (ref "LED3") (pin "A") (pinfunction "A_A") (pintype "passive"))
      (node (ref "R13") (pin "2") (pinfunction "2_2") (pintype "passive"))
    )
    (net (code "15") (name "Net-(LED4-PadA)") (class "Default")
      (node (ref "LED4") (pin "A") (pinfunction "A_A") (pintype "passive"))
      (node (ref "R21") (pin "1") (pinfunction "1_1") (pintype "passive"))
    )
    (net (code "16") (name "Net-(LED5-PadA)") (class "Default")
      (node (ref "LED5") (pin "A") (pinfunction "A_A") (pintype "passive"))
      (node (ref "R23") (pin "2") (pinfunction "2_2") (pintype "passive"))
    )
    (net (code "17") (name "Net-(LED6-PadA)") (class "Default")
      (node (ref "LED6") (pin "A") (pinfunction "A_A") (pintype "passive"))
      (node (ref "R30") (pin "1") (pinfunction "1_1") (pintype "passive"))
    )
    (net (code "18") (name "Net-(Q2-D)") (class "Default")
      (node (ref "Q2") (pin "3") (pinfunction "D_3") (pintype "passive"))
      (node (ref "U$3") (pin "1") (pinfunction "1_1") (pintype "bidirectional"))
    )
    (net (code "19") (name "Net-(Q2-G)") (class "Default")
      (node (ref "Q2") (pin "1") (pinfunction "G_1") (pintype "passive"))
      (node (ref "R7") (pin "2") (pinfunction "2_2") (pintype "passive"))
      (node (ref "R8") (pin "1") (pinfunction "1_1") (pintype "passive"))
    )
    (net (code "20") (name "Net-(Q3-D)") (class "Default")
      (node (ref "Q3") (pin "3") (pinfunction "D_3") (pintype "passive"))
      (node (ref "R16") (pin "1") (pinfunction "1_1") (pintype "passive"))
      (node (ref "TXO2") (pin "1") (pinfunction "P_1") (pintype "passive"))
    )
    (net (code "21") (name "Net-(Q3-S)") (class "Default")
      (node (ref "Q3") (pin "2") (pinfunction "S_2") (pintype "passive"))
      (node (ref "R15") (pin "2") (pinfunction "2_2") (pintype "passive"))
      (node (ref "U1") (pin "3") (pinfunction "TXO/MISO/SCL_3") (pintype "bidirectional"))
    )
    (net (code "22") (name "Net-(Q4-D)") (class "Default")
      (node (ref "Q4") (pin "3") (pinfunction "D_3") (pintype "passive"))
      (node (ref "R17") (pin "1") (pinfunction "1_1") (pintype "passive"))
      (node (ref "RXIH") (pin "1") (pinfunction "P_1") (pintype "passive"))
    )
    (net (code "23") (name "Net-(Q4-S)") (class "Default")
      (node (ref "Q4") (pin "2") (pinfunction "S_2") (pintype "passive"))
      (node (ref "R14") (pin "1") (pinfunction "1_1") (pintype "passive"))
      (node (ref "U1") (pin "10") (pinfunction "RXI/MOSI/SDA_10") (pintype "bidirectional"))
    )
    (net (code "24") (name "Net-(Q5-D)") (class "Default")
      (node (ref "Q5") (pin "3") (pinfunction "D_3") (pintype "passive"))
      (node (ref "U$7") (pin "1") (pinfunction "1_1") (pintype "bidirectional"))
    )
    (net (code "25") (name "Net-(Q5-G)") (class "Default")
      (node (ref "Q5") (pin "1") (pinfunction "G_1") (pintype "passive"))
      (node (ref "R18") (pin "2") (pinfunction "2_2") (pintype "passive"))
      (node (ref "R19") (pin "2") (pinfunction "2_2") (pintype "passive"))
      (node (ref "U$8") (pin "2") (pinfunction "2_2") (pintype "bidirectional"))
    )
    (net (code "26") (name "Net-(RXI_1-P)") (class "Default")
      (node (ref "RXI_1") (pin "1") (pinfunction "P_1") (pintype "passive"))
      (node (ref "RXI_2") (pin "1") (pinfunction "P_1") (pintype "passive"))
      (node (ref "U2") (pin "30") (pinfunction "PD0(RXD)_30") (pintype "bidirectional"))
    )
    (net (code "27") (name "Net-(TP1-PP)") (class "Default")
      (node (ref "C24") (pin "1") (pinfunction "1_1") (pintype "passive"))
      (node (ref "R20") (pin "2") (pinfunction "2_2") (pintype "passive"))
      (node (ref "TP1") (pin "TP") (pinfunction "PP_TP") (pintype "input"))
      (node (ref "U8") (pin "1") (pinfunction "PB5(NRES)_1") (pintype "bidirectional"))
    )
    (net (code "28") (name "Net-(TXO1-P)") (class "Default")
      (node (ref "TXO1") (pin "1") (pinfunction "P_1") (pintype "passive"))
      (node (ref "U3") (pin "18") (pinfunction "TXO_18") (pintype "output"))
    )
    (net (code "29") (name "Net-(TXO_-P)") (class "Default")
      (node (ref "TXO_") (pin "1") (pinfunction "P_1") (pintype "passive"))
      (node (ref "U2") (pin "31") (pinfunction "PD1(TXD)_31") (pintype "bidirectional"))
    )
    (net (code "30") (name "Net-(U1-1PPS)") (class "Default")
      (node (ref "R2") (pin "1") (pinfunction "1_1") (pintype "passive"))
      (node (ref "U1") (pin "2") (pinfunction "1PPS_2") (pintype "output"))
    )
    (net (code "31") (name "Net-(U1-MODE1{slash}SCK{slash}~{CTS})") (class "Default")
      (node (ref "R1") (pin "1") (pinfunction "1_1") (pintype "passive"))
      (node (ref "U1") (pin "7") (pinfunction "MODE1/SCK/~{CTS}_7") (pintype "bidirectional"))
    )
    (net (code "32") (name "Net-(U1-ON{slash}OFF)") (class "Default")
      (node (ref "U1") (pin "1") (pinfunction "ON/OFF_1") (pintype "input"))
      (node (ref "U1") (pin "6") (pinfunction "WAKEUP_6") (pintype "output"))
    )
    (net (code "33") (name "Net-(U2-AREF)") (class "Default")
      (node (ref "C7") (pin "1") (pinfunction "1_1") (pintype "passive"))
      (node (ref "U2") (pin "20") (pinfunction "AREF_20") (pintype "bidirectional"))
    )
    (net (code "34") (name "Net-(U2-PB6(XTAL1{slash}TOSC1))") (class "Default")
      (node (ref "C13") (pin "1") (pinfunction "1_1") (pintype "passive"))
      (node (ref "Q1") (pin "1") (pinfunction "1_1") (pintype "passive"))
      (node (ref "U2") (pin "7") (pinfunction "PB6(XTAL1/TOSC1)_7") (pintype "bidirectional"))
    )
    (net (code "35") (name "Net-(U2-PB7(XTAL2{slash}TOSC2))") (class "Default")
      (node (ref "C12") (pin "1") (pinfunction "1_1") (pintype "passive"))
      (node (ref "Q1") (pin "2") (pinfunction "2_2") (pintype "passive"))
      (node (ref "U2") (pin "8") (pinfunction "PB7(XTAL2/TOSC2)_8") (pintype "bidirectional"))
    )
    (net (code "36") (name "Net-(U2-PD6(AIN0))") (class "Default")
      (node (ref "R8") (pin "2") (pinfunction "2_2") (pintype "passive"))
      (node (ref "U2") (pin "10") (pinfunction "PD6(AIN0)_10") (pintype "bidirectional"))
    )
    (net (code "37") (name "Net-(U3-+3V3)") (class "Default")
      (node (ref "C4") (pin "1") (pinfunction "1_1") (pintype "passive"))
      (node (ref "C5") (pin "1") (pinfunction "1_1") (pintype "passive"))
      (node (ref "C6") (pin "1") (pinfunction "1_1") (pintype "passive"))
      (node (ref "R3") (pin "2") (pinfunction "2_2") (pintype "passive"))
      (node (ref "U3") (pin "3") (pinfunction "+3V3_3") (pintype "power_in"))
      (node (ref "U5") (pin "5") (pinfunction "VOUT_5") (pintype "bidirectional"))
    )
    (net (code "38") (name "Net-(U3-GPIO6)") (class "Default")
      (node (ref "R3") (pin "1") (pinfunction "1_1") (pintype "passive"))
      (node (ref "U3") (pin "7") (pinfunction "GPIO6_7") (pintype "input"))
    )
    (net (code "39") (name "Net-(U3-ON_OFF)") (class "Default")
      (node (ref "U3") (pin "16") (pinfunction "ON_OFF_16") (pintype "input"))
      (node (ref "U3") (pin "4") (pinfunction "WAKEUP_4") (pintype "output"))
    )
    (net (code "40") (name "Net-(U3-TM_GPIO5)") (class "Default")
      (node (ref "R4") (pin "1") (pinfunction "1_1") (pintype "passive"))
      (node (ref "U3") (pin "13") (pinfunction "TM_GPIO5_13") (pintype "output"))
    )
    (net (code "41") (name "Net-(U7-PROG)") (class "Default")
      (node (ref "R12") (pin "1") (pinfunction "1_1") (pintype "passive"))
      (node (ref "U7") (pin "5") (pinfunction "PROG_5") (pintype "input"))
    )
    (net (code "42") (name "Net-(U7-STAT)") (class "Default")
      (node (ref "LED3") (pin "C") (pinfunction "C_C") (pintype "passive"))
      (node (ref "U7") (pin "1") (pinfunction "STAT_1") (pintype "output"))
    )
    (net (code "43") (name "Net-(U7-VIN)") (class "Default")
      (node (ref "C15") (pin "1") (pinfunction "1_1") (pintype "passive"))
      (node (ref "R13") (pin "1") (pinfunction "1_1") (pintype "passive"))
      (node (ref "U$4") (pin "1") (pinfunction "1_1") (pintype "bidirectional"))
      (node (ref "U7") (pin "4") (pinfunction "VIN_4") (pintype "power_in"))
    )
    (net (code "44") (name "Net-(U9-C1)") (class "Default")
      (node (ref "C27") (pin "2") (pinfunction "2_2") (pintype "passive"))
      (node (ref "U9") (pin "4") (pinfunction "C1_4") (pintype "bidirectional"))
    )
    (net (code "45") (name "Net-(U10-PROG)") (class "Default")
      (node (ref "R22") (pin "1") (pinfunction "1_1") (pintype "passive"))
      (node (ref "U10") (pin "5") (pinfunction "PROG_5") (pintype "input"))
    )
    (net (code "46") (name "Net-(U10-STAT)") (class "Default")
      (node (ref "LED5") (pin "C") (pinfunction "C_C") (pintype "passive"))
      (node (ref "U10") (pin "1") (pinfunction "STAT_1") (pintype "output"))
    )
    (net (code "47") (name "Net-(U10-VIN)") (class "Default")
      (node (ref "C29") (pin "1") (pinfunction "1_1") (pintype "passive"))
      (node (ref "R23") (pin "1") (pinfunction "1_1") (pintype "passive"))
      (node (ref "U$9") (pin "1") (pinfunction "1_1") (pintype "bidirectional"))
      (node (ref "U10") (pin "4") (pinfunction "VIN_4") (pintype "power_in"))
    )
    (net (code "48") (name "Net-(U11-EN)") (class "Default")
      (node (ref "R27") (pin "2") (pinfunction "2_2") (pintype "passive"))
      (node (ref "U11") (pin "3") (pinfunction "EN_3") (pintype "bidirectional"))
    )
    (net (code "49") (name "PYRO") (class "Default")
      (node (ref "R18") (pin "1") (pinfunction "1_1") (pintype "passive"))
      (node (ref "R21") (pin "2") (pinfunction "2_2") (pintype "passive"))
      (node (ref "U8") (pin "2") (pinfunction "PB3(ADC3)_2") (pintype "bidirectional"))
    )
    (net (code "50") (name "RF_RTTY") (class "Default")
      (node (ref "U$1") (pin "DIO2") (pinfunction "DIO2_DIO2") (pintype "bidirectional"))
      (node (ref "U2") (pin "24") (pinfunction "PC1(ADC1)_24") (pintype "bidirectional"))
    )
    (net (code "51") (name "SCK") (class "Default")
      (node (ref "SCK") (pin "1") (pinfunction "P_1") (pintype "passive"))
      (node (ref "U$1") (pin "SCK") (pinfunction "SCK_SCK") (pintype "bidirectional"))
      (node (ref "U2") (pin "17") (pinfunction "PB5(SCK)_17") (pintype "bidirectional"))
    )
    (net (code "52") (name "SCL") (class "Default")
      (node (ref "IC1") (pin "3") (pinfunction "SCL_3") (pintype "bidirectional"))
      (node (ref "R25") (pin "2") (pinfunction "2_2") (pintype "passive"))
      (node (ref "U8") (pin "7") (pinfunction "PB2(SCK/ADC1)_7") (pintype "bidirectional"))
      (node (ref "U9") (pin "1") (pinfunction "SCL/SPC_1") (pintype "bidirectional"))
    )
    (net (code "53") (name "SDA") (class "Default")
      (node (ref "IC1") (pin "2") (pinfunction "SDA_2") (pintype "bidirectional"))
      (node (ref "R24") (pin "2") (pinfunction "2_2") (pintype "passive"))
      (node (ref "U8") (pin "5") (pinfunction "PB0(MOSI)_5") (pintype "bidirectional"))
      (node (ref "U9") (pin "11") (pinfunction "SDA/SDI_11") (pintype "bidirectional"))
    )
    (net (code "54") (name "UART") (class "Default")
      (node (ref "U$6") (pin "2") (pinfunction "2_2") (pintype "bidirectional"))
      (node (ref "U8") (pin "3") (pinfunction "PB4(ADC2)_3") (pintype "bidirectional"))
    )
    (net (code "55") (name "V+") (class "Default")
      (node (ref "C1") (pin "1") (pinfunction "1_1") (pintype "passive"))
      (node (ref "C2") (pin "1") (pinfunction "1_1") (pintype "passive"))
      (node (ref "C3") (pin "1") (pinfunction "1_1") (pintype "passive"))
      (node (ref "Q3") (pin "1") (pinfunction "G_1") (pintype "passive"))
      (node (ref "Q4") (pin "1") (pinfunction "G_1") (pintype "passive"))
      (node (ref "R1") (pin "2") (pinfunction "2_2") (pintype "passive"))
      (node (ref "R14") (pin "2") (pinfunction "2_2") (pintype "passive"))
      (node (ref "R15") (pin "1") (pinfunction "1_1") (pintype "passive"))
      (node (ref "U1") (pin "4") (pinfunction "+1V8_4") (pintype "power_in"))
      (node (ref "U4") (pin "5") (pinfunction "VOUT_5") (pintype "bidirectional"))
    )
    (net (code "56") (name "VBAT") (class "Default")
      (node (ref "C25") (pin "1") (pinfunction "1_1") (pintype "passive"))
      (node (ref "R27") (pin "1") (pinfunction "1_1") (pintype "passive"))
      (node (ref "U$5") (pin "1") (pinfunction "1_1") (pintype "bidirectional"))
      (node (ref "U$7") (pin "2") (pinfunction "2_2") (pintype "bidirectional"))
      (node (ref "U10") (pin "3") (pinfunction "VBAT_3") (pintype "power_in"))
      (node (ref "U11") (pin "1") (pinfunction "VIN_1") (pintype "bidirectional"))
    )
    (net (code "57") (name "VCC") (class "Default")
      (node (ref "C22") (pin "1") (pinfunction "1_1") (pintype "passive"))
      (node (ref "C23") (pin "1") (pinfunction "1_1") (pintype "passive"))
      (node (ref "C26") (pin "1") (pinfunction "1_1") (pintype "passive"))
      (node (ref "C28") (pin "1") (pinfunction "1_1") (pintype "passive"))
      (node (ref "IC1") (pin "1") (pinfunction "VDD_1") (pintype "bidirectional"))
      (node (ref "R20") (pin "1") (pinfunction "1_1") (pintype "passive"))
      (node (ref "R24") (pin "1") (pinfunction "1_1") (pintype "passive"))
      (node (ref "R25") (pin "1") (pinfunction "1_1") (pintype "passive"))
      (node (ref "U11") (pin "5") (pinfunction "VOUT_5") (pintype "bidirectional"))
      (node (ref "U8") (pin "8") (pinfunction "VCC_8") (pintype "bidirectional"))
      (node (ref "U9") (pin "10") (pinfunction "CS_10") (pintype "bidirectional"))
      (node (ref "U9") (pin "5") (pinfunction "VDD_5") (pintype "bidirectional"))
      (node (ref "U9") (pin "6") (pinfunction "VDD_IO_6") (pintype "power_in"))
      (node (ref "U9") (pin "9") (pinfunction "SD0/SA1_9") (pintype "bidirectional"))
    )
    (net (code "58") (name "VOUT") (class "Default")
      (node (ref "U3") (pin "5") (pinfunction "VOUT_5") (pintype "power_in"))
    )
    (net (code "59") (name "unconnected-(U$1-PadDIO0)") (class "Default")
      (node (ref "U$1") (pin "DIO0") (pinfunction "DIO0_DIO0") (pintype "bidirectional"))
    )
    (net (code "60") (name "unconnected-(U$1-PadDIO1)") (class "Default")
      (node (ref "U$1") (pin "DIO1") (pinfunction "DIO1_DIO1") (pintype "bidirectional"))
    )
    (net (code "61") (name "unconnected-(U$1-PadDIO3)") (class "Default")
      (node (ref "U$1") (pin "DIO3") (pinfunction "DIO3_DIO3") (pintype "bidirectional"))
    )
    (net (code "62") (name "unconnected-(U$1-PadDIO4)") (class "Default")
      (node (ref "U$1") (pin "DIO4") (pinfunction "DIO4_DIO4") (pintype "bidirectional"))
    )
    (net (code "63") (name "unconnected-(U$1-PadDIO5)") (class "Default")
      (node (ref "U$1") (pin "DIO5") (pinfunction "DIO5_DIO5") (pintype "bidirectional"))
    )
    (net (code "64") (name "unconnected-(U$1-PadNC)") (class "Default")
      (node (ref "U$1") (pin "NC") (pinfunction "NC_NC") (pintype "bidirectional"))
    )
    (net (code "65") (name "unconnected-(U1-MODE2{slash}~{CS{slash}}RTS-Pad9)") (class "Default")
      (node (ref "U1") (pin "9") (pinfunction "MODE2/~{CS/}RTS_9") (pintype "bidirectional"))
    )
    (net (code "66") (name "unconnected-(U1-~{RESET}-Pad8)") (class "Default")
      (node (ref "U1") (pin "8") (pinfunction "~{RESET}_8") (pintype "input"))
    )
    (net (code "67") (name "unconnected-(U2-ADC6-Pad19)") (class "Default")
      (node (ref "U2") (pin "19") (pinfunction "ADC6_19") (pintype "bidirectional"))
    )
    (net (code "68") (name "unconnected-(U2-ADC7-Pad22)") (class "Default")
      (node (ref "U2") (pin "22") (pinfunction "ADC7_22") (pintype "bidirectional"))
    )
    (net (code "69") (name "unconnected-(U2-PB0(ICP)-Pad12)") (class "Default")
      (node (ref "U2") (pin "12") (pinfunction "PB0(ICP)_12") (pintype "bidirectional"))
    )
    (net (code "70") (name "unconnected-(U2-PB2(SS{slash}OC1B)-Pad14)") (class "Default")
      (node (ref "U2") (pin "14") (pinfunction "PB2(SS/OC1B)_14") (pintype "bidirectional"))
    )
    (net (code "71") (name "unconnected-(U2-PC0(ADC0)-Pad23)") (class "Default")
      (node (ref "U2") (pin "23") (pinfunction "PC0(ADC0)_23") (pintype "bidirectional"))
    )
    (net (code "72") (name "unconnected-(U2-PC2(ADC2)-Pad25)") (class "Default")
      (node (ref "U2") (pin "25") (pinfunction "PC2(ADC2)_25") (pintype "bidirectional"))
    )
    (net (code "73") (name "unconnected-(U2-PC4(ADC4{slash}SDA)-Pad27)") (class "Default")
      (node (ref "U2") (pin "27") (pinfunction "PC4(ADC4/SDA)_27") (pintype "bidirectional"))
    )
    (net (code "74") (name "unconnected-(U2-PC5(ADC5{slash}SCL)-Pad28)") (class "Default")
      (node (ref "U2") (pin "28") (pinfunction "PC5(ADC5/SCL)_28") (pintype "bidirectional"))
    )
    (net (code "75") (name "unconnected-(U2-PD3(INT1)-Pad1)") (class "Default")
      (node (ref "U2") (pin "1") (pinfunction "PD3(INT1)_1") (pintype "bidirectional"))
    )
    (net (code "76") (name "unconnected-(U2-PD4(XCK{slash}T0)-Pad2)") (class "Default")
      (node (ref "U2") (pin "2") (pinfunction "PD4(XCK/T0)_2") (pintype "bidirectional"))
    )
    (net (code "77") (name "unconnected-(U2-PD5(T1)-Pad9)") (class "Default")
      (node (ref "U2") (pin "9") (pinfunction "PD5(T1)_9") (pintype "bidirectional"))
    )
    (net (code "78") (name "unconnected-(U3-GPIO4-Pad12)") (class "Default")
      (node (ref "U3") (pin "12") (pinfunction "GPIO4_12") (pintype "input"))
    )
    (net (code "79") (name "unconnected-(U3-GPIO7-Pad8)") (class "Default")
      (node (ref "U3") (pin "8") (pinfunction "GPIO7_8") (pintype "input"))
    )
    (net (code "80") (name "unconnected-(U3-HOST_SCL-Pad11)") (class "Default")
      (node (ref "U3") (pin "11") (pinfunction "HOST_SCL_11") (pintype "input"))
    )
    (net (code "81") (name "unconnected-(U3-NC2-Pad2)") (class "Default")
      (node (ref "U3") (pin "2") (pinfunction "NC2_2") (pintype "no_connect"))
    )
    (net (code "82") (name "unconnected-(U3-NC10-Pad10)") (class "Default")
      (node (ref "U3") (pin "10") (pinfunction "NC10_10") (pintype "no_connect"))
    )
    (net (code "83") (name "unconnected-(U3-RXI-Pad19)") (class "Default")
      (node (ref "U3") (pin "19") (pinfunction "RXI_19") (pintype "input"))
    )
    (net (code "84") (name "unconnected-(U3-SCL-Pad14)") (class "Default")
      (node (ref "U3") (pin "14") (pinfunction "SCL_14") (pintype "input"))
    )
    (net (code "85") (name "unconnected-(U3-SDA-Pad15)") (class "Default")
      (node (ref "U3") (pin "15") (pinfunction "SDA_15") (pintype "bidirectional"))
    )
    (net (code "86") (name "unconnected-(U3-~{RST}-Pad1)") (class "Default")
      (node (ref "U3") (pin "1") (pinfunction "~{RST}_1") (pintype "input"))
    )
    (net (code "87") (name "unconnected-(U9-DRDY-Pad8)") (class "Default")
      (node (ref "U9") (pin "8") (pinfunction "DRDY_8") (pintype "bidirectional"))
    )
    (net (code "88") (name "unconnected-(U9-INT-Pad7)") (class "Default")
      (node (ref "U9") (pin "7") (pinfunction "INT_7") (pintype "bidirectional"))
    )
    (net (code "89") (name "~{CS}") (class "Default")
      (node (ref "R11") (pin "2") (pinfunction "2_2") (pintype "passive"))
      (node (ref "U$1") (pin "NSS") (pinfunction "NSS_NSS") (pintype "bidirectional"))
      (node (ref "U2") (pin "13") (pinfunction "PB1(OC1A)_13") (pintype "bidirectional"))
    )
    (net (code "90") (name "~{RF_RES}") (class "Default")
      (node (ref "U$1") (pin "RESET") (pinfunction "RESET_RESET") (pintype "bidirectional"))
      (node (ref "U2") (pin "32") (pinfunction "PD2(INT0)_32") (pintype "bidirectional"))
    )
  )
)
